# project_1_2.net
KiCad netlist of a schematic drawn in Altium Designer
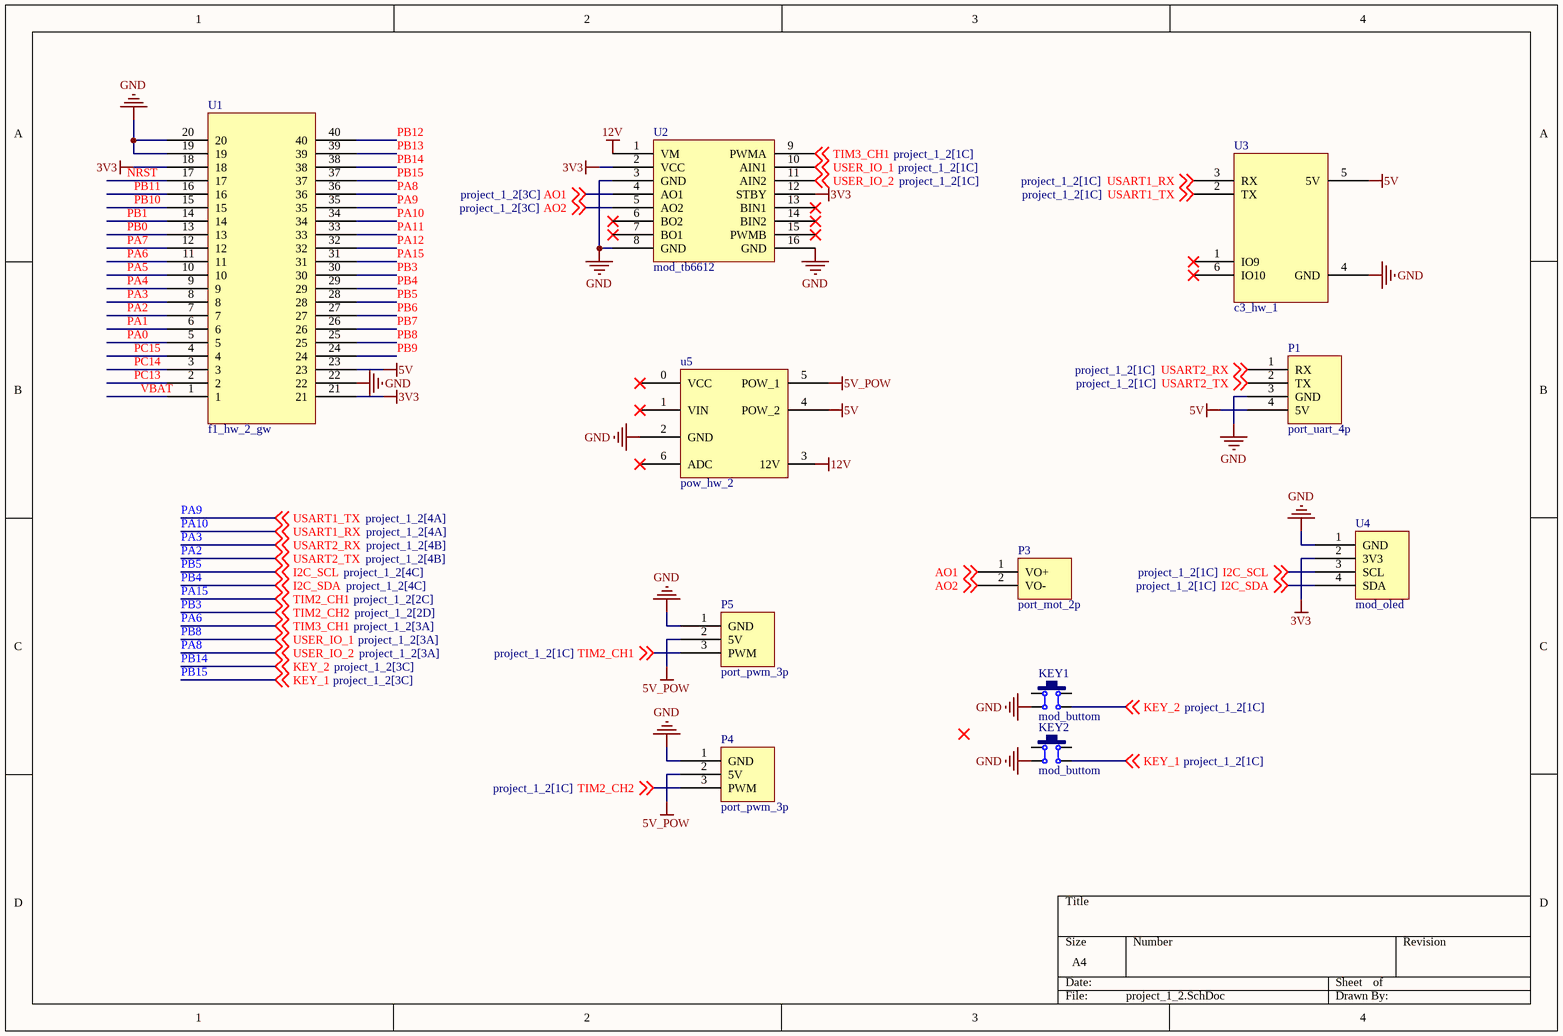
[diagram p0: project_1_2.SchDoc]

(export (version "E")
  (design (tool "Eeschema 10.0.6"))
  (components
    (comp (ref "KEY1")
      (value "mod_buttom")
      (footprint "MOD_BUTTOM")
      (description "6*6*4.3按键")
      (libsource (lib "userLib") (part "mod_buttom"))
    )
    (comp (ref "KEY2")
      (value "mod_buttom")
      (footprint "MOD_BUTTOM")
      (description "6*6*4.3按键")
      (libsource (lib "userLib") (part "mod_buttom"))
    )
    (comp (ref "P1")
      (value "port_uart_4p")
      (footprint "XH2.54_4P")
      (description "串口接口/SPP蓝牙模块\r\nXH2.54弯排针4p/4p排母")
      (libsource (lib "userLib") (part "port_uart_4p"))
    )
    (comp (ref "P3")
      (value "port_mot_2p")
      (footprint "XH2.54_2P")
      (description "开环直流电机接口\r\nXH2.54弯排针2p")
      (libsource (lib "userLib") (part "port_mot_2p"))
    )
    (comp (ref "P4")
      (value "port_pwm_3p")
      (footprint "XH2.54_3P")
      (description "舵机接口\r\nXH2.54弯排针3p")
      (libsource (lib "userLib") (part "port_pwm_3p"))
    )
    (comp (ref "P5")
      (value "port_pwm_3p")
      (footprint "XH2.54_3P")
      (description "舵机接口\r\nXH2.54弯排针3p")
      (libsource (lib "userLib") (part "port_pwm_3p"))
    )
    (comp (ref "U1")
      (value "f1_hw_2_gw")
      (footprint "F1_HW_2_GW")
      (libsource (lib "userLib") (part "f1_hw_2_gw"))
    )
    (comp (ref "U2")
      (value "mod_tb6612")
      (footprint "MOD_TB6612")
      (description "TB6612模块\r\n8p排母*2")
      (libsource (lib "userLib") (part "mod_tb6612"))
    )
    (comp (ref "U3")
      (value "c3_hw_1")
      (footprint "C3_HW_1")
      (description "ESP32C3蓝牙模块\r\n6p排母")
      (libsource (lib "userLib") (part "c3_hw_1"))
    )
    (comp (ref "U4")
      (value "mod_oled")
      (footprint "mod_oled")
      (description "外购屏幕模块")
      (libsource (lib "userLib") (part "mod_oled"))
    )
    (comp (ref "u5")
      (value "pow_hw_2")
      (footprint "POW_HW_2")
      (description "两路升降压电源模块\r\n6p排母*2")
      (libsource (lib "userLib") (part "pow_hw_2"))
    )
  )
  (nets
    (net (code "1") (name "/NRST") (class "Default")
      (node (ref "U1") (pin "17") (pinfunction "17_17") (pintype "passive"))
    )
    (net (code "2") (name "/PA0") (class "Default")
      (node (ref "U1") (pin "5") (pinfunction "5_5") (pintype "passive"))
    )
    (net (code "3") (name "/PA1") (class "Default")
      (node (ref "U1") (pin "6") (pinfunction "6_6") (pintype "passive"))
    )
    (net (code "4") (name "/PA4") (class "Default")
      (node (ref "U1") (pin "9") (pinfunction "9_9") (pintype "passive"))
    )
    (net (code "5") (name "/PA5") (class "Default")
      (node (ref "U1") (pin "10") (pinfunction "10_10") (pintype "passive"))
    )
    (net (code "6") (name "/PA7") (class "Default")
      (node (ref "U1") (pin "12") (pinfunction "12_12") (pintype "passive"))
    )
    (net (code "7") (name "/PA11") (class "Default")
      (node (ref "U1") (pin "33") (pinfunction "33_33") (pintype "passive"))
    )
    (net (code "8") (name "/PA12") (class "Default")
      (node (ref "U1") (pin "32") (pinfunction "32_32") (pintype "passive"))
    )
    (net (code "9") (name "/PB0") (class "Default")
      (node (ref "U1") (pin "13") (pinfunction "13_13") (pintype "passive"))
    )
    (net (code "10") (name "/PB1") (class "Default")
      (node (ref "U1") (pin "14") (pinfunction "14_14") (pintype "passive"))
    )
    (net (code "11") (name "/PB6") (class "Default")
      (node (ref "U1") (pin "27") (pinfunction "27_27") (pintype "passive"))
    )
    (net (code "12") (name "/PB7") (class "Default")
      (node (ref "U1") (pin "26") (pinfunction "26_26") (pintype "passive"))
    )
    (net (code "13") (name "/PB9") (class "Default")
      (node (ref "U1") (pin "24") (pinfunction "24_24") (pintype "passive"))
    )
    (net (code "14") (name "/PB10") (class "Default")
      (node (ref "U1") (pin "15") (pinfunction "15_15") (pintype "passive"))
    )
    (net (code "15") (name "/PB11") (class "Default")
      (node (ref "U1") (pin "16") (pinfunction "16_16") (pintype "passive"))
    )
    (net (code "16") (name "/PB12") (class "Default")
      (node (ref "U1") (pin "40") (pinfunction "40_40") (pintype "passive"))
    )
    (net (code "17") (name "/PB13") (class "Default")
      (node (ref "U1") (pin "39") (pinfunction "39_39") (pintype "passive"))
    )
    (net (code "18") (name "/PC13") (class "Default")
      (node (ref "U1") (pin "2") (pinfunction "2_2") (pintype "passive"))
    )
    (net (code "19") (name "/PC14") (class "Default")
      (node (ref "U1") (pin "3") (pinfunction "3_3") (pintype "passive"))
    )
    (net (code "20") (name "/PC15") (class "Default")
      (node (ref "U1") (pin "4") (pinfunction "4_4") (pintype "passive"))
    )
    (net (code "21") (name "/VBAT") (class "Default")
      (node (ref "U1") (pin "1") (pinfunction "1_1") (pintype "passive"))
    )
    (net (code "22") (name "3V3") (class "Default")
      (node (ref "U1") (pin "18") (pinfunction "18_18") (pintype "passive"))
      (node (ref "U1") (pin "21") (pinfunction "21_21") (pintype "passive"))
      (node (ref "U2") (pin "12") (pinfunction "STBY_12") (pintype "passive"))
      (node (ref "U2") (pin "2") (pinfunction "VCC_2") (pintype "passive"))
      (node (ref "U4") (pin "2") (pinfunction "3V3_2") (pintype "passive"))
    )
    (net (code "23") (name "5V") (class "Default")
      (node (ref "P1") (pin "4") (pinfunction "5V_4") (pintype "passive"))
      (node (ref "U1") (pin "23") (pinfunction "23_23") (pintype "passive"))
      (node (ref "U3") (pin "5") (pinfunction "5V_5") (pintype "passive"))
      (node (ref "u5") (pin "4") (pinfunction "POW_2_4") (pintype "passive"))
    )
    (net (code "24") (name "5V_POW") (class "Default")
      (node (ref "P4") (pin "2") (pinfunction "5V_2") (pintype "passive"))
      (node (ref "P5") (pin "2") (pinfunction "5V_2") (pintype "passive"))
      (node (ref "u5") (pin "5") (pinfunction "POW_1_5") (pintype "passive"))
    )
    (net (code "25") (name "12V") (class "Default")
      (node (ref "U2") (pin "1") (pinfunction "VM_1") (pintype "passive"))
    )
    (net (code "26") (name "AO1") (class "Default")
      (node (ref "P3") (pin "1") (pinfunction "VO+_1") (pintype "passive"))
      (node (ref "U2") (pin "4") (pinfunction "AO1_4") (pintype "passive"))
    )
    (net (code "27") (name "AO2") (class "Default")
      (node (ref "P3") (pin "2") (pinfunction "VO-_2") (pintype "passive"))
      (node (ref "U2") (pin "5") (pinfunction "AO2_5") (pintype "passive"))
    )
    (net (code "28") (name "GND") (class "Default")
      (node (ref "KEY1") (pin "4") (pinfunction "4_4") (pintype "passive"))
      (node (ref "KEY2") (pin "4") (pinfunction "4_4") (pintype "passive"))
      (node (ref "P1") (pin "3") (pinfunction "GND_3") (pintype "passive"))
      (node (ref "P4") (pin "1") (pinfunction "GND_1") (pintype "passive"))
      (node (ref "P5") (pin "1") (pinfunction "GND_1") (pintype "passive"))
      (node (ref "U1") (pin "19") (pinfunction "19_19") (pintype "passive"))
      (node (ref "U1") (pin "20") (pinfunction "20_20") (pintype "passive"))
      (node (ref "U1") (pin "22") (pinfunction "22_22") (pintype "passive"))
      (node (ref "U2") (pin "16") (pinfunction "GND_16") (pintype "passive"))
      (node (ref "U2") (pin "3") (pinfunction "GND_3") (pintype "passive"))
      (node (ref "U2") (pin "8") (pinfunction "GND_8") (pintype "passive"))
      (node (ref "U3") (pin "4") (pinfunction "GND_4") (pintype "passive"))
      (node (ref "U4") (pin "1") (pinfunction "GND_1") (pintype "passive"))
      (node (ref "u5") (pin "2") (pinfunction "GND_2") (pintype "passive"))
    )
    (net (code "29") (name "I2C_SCL") (class "Default")
      (node (ref "U1") (pin "28") (pinfunction "28_28") (pintype "passive"))
      (node (ref "U4") (pin "3") (pinfunction "SCL_3") (pintype "passive"))
    )
    (net (code "30") (name "I2C_SDA") (class "Default")
      (node (ref "U1") (pin "29") (pinfunction "29_29") (pintype "passive"))
      (node (ref "U4") (pin "4") (pinfunction "SDA_4") (pintype "passive"))
    )
    (net (code "31") (name "KEY_1") (class "Default")
      (node (ref "KEY2") (pin "3") (pinfunction "3_3") (pintype "passive"))
      (node (ref "U1") (pin "37") (pinfunction "37_37") (pintype "passive"))
    )
    (net (code "32") (name "KEY_2") (class "Default")
      (node (ref "KEY1") (pin "3") (pinfunction "3_3") (pintype "passive"))
      (node (ref "U1") (pin "38") (pinfunction "38_38") (pintype "passive"))
    )
    (net (code "33") (name "TIM2_CH1") (class "Default")
      (node (ref "P5") (pin "3") (pinfunction "PWM_3") (pintype "passive"))
      (node (ref "U1") (pin "31") (pinfunction "31_31") (pintype "passive"))
    )
    (net (code "34") (name "TIM2_CH2") (class "Default")
      (node (ref "P4") (pin "3") (pinfunction "PWM_3") (pintype "passive"))
      (node (ref "U1") (pin "30") (pinfunction "30_30") (pintype "passive"))
    )
    (net (code "35") (name "TIM3_CH1") (class "Default")
      (node (ref "U1") (pin "11") (pinfunction "11_11") (pintype "passive"))
      (node (ref "U2") (pin "9") (pinfunction "PWMA_9") (pintype "passive"))
    )
    (net (code "36") (name "USART1_RX") (class "Default")
      (node (ref "U1") (pin "34") (pinfunction "34_34") (pintype "passive"))
      (node (ref "U3") (pin "3") (pinfunction "RX_3") (pintype "passive"))
    )
    (net (code "37") (name "USART1_TX") (class "Default")
      (node (ref "U1") (pin "35") (pinfunction "35_35") (pintype "passive"))
      (node (ref "U3") (pin "2") (pinfunction "TX_2") (pintype "passive"))
    )
    (net (code "38") (name "USART2_RX") (class "Default")
      (node (ref "P1") (pin "1") (pinfunction "RX_1") (pintype "passive"))
      (node (ref "U1") (pin "8") (pinfunction "8_8") (pintype "passive"))
    )
    (net (code "39") (name "USART2_TX") (class "Default")
      (node (ref "P1") (pin "2") (pinfunction "TX_2") (pintype "passive"))
      (node (ref "U1") (pin "7") (pinfunction "7_7") (pintype "passive"))
    )
    (net (code "40") (name "USER_IO_1") (class "Default")
      (node (ref "U1") (pin "25") (pinfunction "25_25") (pintype "passive"))
      (node (ref "U2") (pin "10") (pinfunction "AIN1_10") (pintype "passive"))
    )
    (net (code "41") (name "USER_IO_2") (class "Default")
      (node (ref "U1") (pin "36") (pinfunction "36_36") (pintype "passive"))
      (node (ref "U2") (pin "11") (pinfunction "AIN2_11") (pintype "passive"))
    )
    (net (code "42") (name "unconnected-(KEY1-Pad1)") (class "Default")
      (node (ref "KEY1") (pin "1") (pinfunction "1_1") (pintype "passive"))
    )
    (net (code "43") (name "unconnected-(KEY1-Pad2)") (class "Default")
      (node (ref "KEY1") (pin "2") (pinfunction "2_2") (pintype "passive"))
    )
    (net (code "44") (name "unconnected-(KEY2-Pad1)") (class "Default")
      (node (ref "KEY2") (pin "1") (pinfunction "1_1") (pintype "passive"))
    )
    (net (code "45") (name "unconnected-(KEY2-Pad2)") (class "Default")
      (node (ref "KEY2") (pin "2") (pinfunction "2_2") (pintype "passive"))
    )
    (net (code "46") (name "unconnected-(U2-BIN1-Pad13)") (class "Default")
      (node (ref "U2") (pin "13") (pinfunction "BIN1_13") (pintype "passive+no_connect"))
    )
    (net (code "47") (name "unconnected-(U2-BIN2-Pad14)") (class "Default")
      (node (ref "U2") (pin "14") (pinfunction "BIN2_14") (pintype "passive+no_connect"))
    )
    (net (code "48") (name "unconnected-(U2-BO1-Pad7)") (class "Default")
      (node (ref "U2") (pin "7") (pinfunction "BO1_7") (pintype "passive+no_connect"))
    )
    (net (code "49") (name "unconnected-(U2-BO2-Pad6)") (class "Default")
      (node (ref "U2") (pin "6") (pinfunction "BO2_6") (pintype "passive+no_connect"))
    )
    (net (code "50") (name "unconnected-(U2-PWMB-Pad15)") (class "Default")
      (node (ref "U2") (pin "15") (pinfunction "PWMB_15") (pintype "passive+no_connect"))
    )
    (net (code "51") (name "unconnected-(U3-IO9-Pad1)") (class "Default")
      (node (ref "U3") (pin "1") (pinfunction "IO9_1") (pintype "passive+no_connect"))
    )
    (net (code "52") (name "unconnected-(U3-IO10-Pad6)") (class "Default")
      (node (ref "U3") (pin "6") (pinfunction "IO10_6") (pintype "passive+no_connect"))
    )
    (net (code "53") (name "unconnected-(u5-12V-Pad3)") (class "Default")
      (node (ref "u5") (pin "3") (pinfunction "12V_3") (pintype "passive"))
    )
    (net (code "54") (name "unconnected-(u5-ADC-Pad6)") (class "Default")
      (node (ref "u5") (pin "6") (pinfunction "ADC_6") (pintype "passive+no_connect"))
    )
    (net (code "55") (name "unconnected-(u5-VCC-Pad0)") (class "Default")
      (node (ref "u5") (pin "0") (pinfunction "VCC_0") (pintype "passive+no_connect"))
    )
    (net (code "56") (name "unconnected-(u5-VIN-Pad1)") (class "Default")
      (node (ref "u5") (pin "1") (pinfunction "VIN_1") (pintype "passive+no_connect"))
    )
  )
)
